# bnc.net
KiCad netlist of a schematic drawn in EAGLE
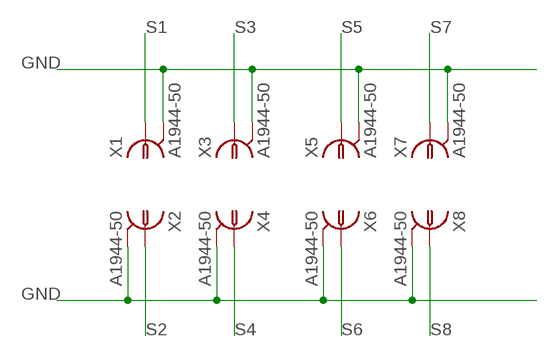
[diagram p0: schematic, sheet 1]

(export (version "E")
  (design (tool "Eeschema 10.0.6"))
  (components
    (comp (ref "X1")
      (value "A1944-50")
      (footprint "eagle-import:A1944")
      (libsource (lib "eagle-import") (part "A1944-50"))
    )
    (comp (ref "X2")
      (value "A1944-50")
      (footprint "eagle-import:A1944")
      (libsource (lib "eagle-import") (part "A1944-50"))
    )
    (comp (ref "X3")
      (value "A1944-50")
      (footprint "eagle-import:A1944")
      (libsource (lib "eagle-import") (part "A1944-50"))
    )
    (comp (ref "X4")
      (value "A1944-50")
      (footprint "eagle-import:A1944")
      (libsource (lib "eagle-import") (part "A1944-50"))
    )
    (comp (ref "X5")
      (value "A1944-50")
      (footprint "eagle-import:A1944")
      (libsource (lib "eagle-import") (part "A1944-50"))
    )
    (comp (ref "X6")
      (value "A1944-50")
      (footprint "eagle-import:A1944")
      (libsource (lib "eagle-import") (part "A1944-50"))
    )
    (comp (ref "X7")
      (value "A1944-50")
      (footprint "eagle-import:A1944")
      (libsource (lib "eagle-import") (part "A1944-50"))
    )
    (comp (ref "X8")
      (value "A1944-50")
      (footprint "eagle-import:A1944")
      (libsource (lib "eagle-import") (part "A1944-50"))
    )
  )
  (nets
    (net (code "1") (name "/GND") (class "Default")
      (node (ref "X1") (pin "2") (pinfunction "2_2") (pintype "passive"))
      (node (ref "X1") (pin "3") (pinfunction "2_3") (pintype "passive"))
      (node (ref "X1") (pin "4") (pinfunction "2_4") (pintype "passive"))
      (node (ref "X1") (pin "5") (pinfunction "2_5") (pintype "passive"))
      (node (ref "X2") (pin "2") (pinfunction "2_2") (pintype "passive"))
      (node (ref "X2") (pin "3") (pinfunction "2_3") (pintype "passive"))
      (node (ref "X2") (pin "4") (pinfunction "2_4") (pintype "passive"))
      (node (ref "X2") (pin "5") (pinfunction "2_5") (pintype "passive"))
      (node (ref "X3") (pin "2") (pinfunction "2_2") (pintype "passive"))
      (node (ref "X3") (pin "3") (pinfunction "2_3") (pintype "passive"))
      (node (ref "X3") (pin "4") (pinfunction "2_4") (pintype "passive"))
      (node (ref "X3") (pin "5") (pinfunction "2_5") (pintype "passive"))
      (node (ref "X4") (pin "2") (pinfunction "2_2") (pintype "passive"))
      (node (ref "X4") (pin "3") (pinfunction "2_3") (pintype "passive"))
      (node (ref "X4") (pin "4") (pinfunction "2_4") (pintype "passive"))
      (node (ref "X4") (pin "5") (pinfunction "2_5") (pintype "passive"))
      (node (ref "X5") (pin "2") (pinfunction "2_2") (pintype "passive"))
      (node (ref "X5") (pin "3") (pinfunction "2_3") (pintype "passive"))
      (node (ref "X5") (pin "4") (pinfunction "2_4") (pintype "passive"))
      (node (ref "X5") (pin "5") (pinfunction "2_5") (pintype "passive"))
      (node (ref "X6") (pin "2") (pinfunction "2_2") (pintype "passive"))
      (node (ref "X6") (pin "3") (pinfunction "2_3") (pintype "passive"))
      (node (ref "X6") (pin "4") (pinfunction "2_4") (pintype "passive"))
      (node (ref "X6") (pin "5") (pinfunction "2_5") (pintype "passive"))
      (node (ref "X7") (pin "2") (pinfunction "2_2") (pintype "passive"))
      (node (ref "X7") (pin "3") (pinfunction "2_3") (pintype "passive"))
      (node (ref "X7") (pin "4") (pinfunction "2_4") (pintype "passive"))
      (node (ref "X7") (pin "5") (pinfunction "2_5") (pintype "passive"))
      (node (ref "X8") (pin "2") (pinfunction "2_2") (pintype "passive"))
      (node (ref "X8") (pin "3") (pinfunction "2_3") (pintype "passive"))
      (node (ref "X8") (pin "4") (pinfunction "2_4") (pintype "passive"))
      (node (ref "X8") (pin "5") (pinfunction "2_5") (pintype "passive"))
    )
    (net (code "2") (name "/S1") (class "Default")
      (node (ref "X1") (pin "1") (pinfunction "1_1") (pintype "passive"))
    )
    (net (code "3") (name "/S2") (class "Default")
      (node (ref "X2") (pin "1") (pinfunction "1_1") (pintype "passive"))
    )
    (net (code "4") (name "/S3") (class "Default")
      (node (ref "X3") (pin "1") (pinfunction "1_1") (pintype "passive"))
    )
    (net (code "5") (name "/S4") (class "Default")
      (node (ref "X4") (pin "1") (pinfunction "1_1") (pintype "passive"))
    )
    (net (code "6") (name "/S5") (class "Default")
      (node (ref "X5") (pin "1") (pinfunction "1_1") (pintype "passive"))
    )
    (net (code "7") (name "/S6") (class "Default")
      (node (ref "X6") (pin "1") (pinfunction "1_1") (pintype "passive"))
    )
    (net (code "8") (name "/S7") (class "Default")
      (node (ref "X7") (pin "1") (pinfunction "1_1") (pintype "passive"))
    )
    (net (code "9") (name "/S8") (class "Default")
      (node (ref "X8") (pin "1") (pinfunction "1_1") (pintype "passive"))
    )
  )
)
